# Tortoise_Matrix_Board_schematic.net
KiCad netlist of a schematic drawn in EasyEDA
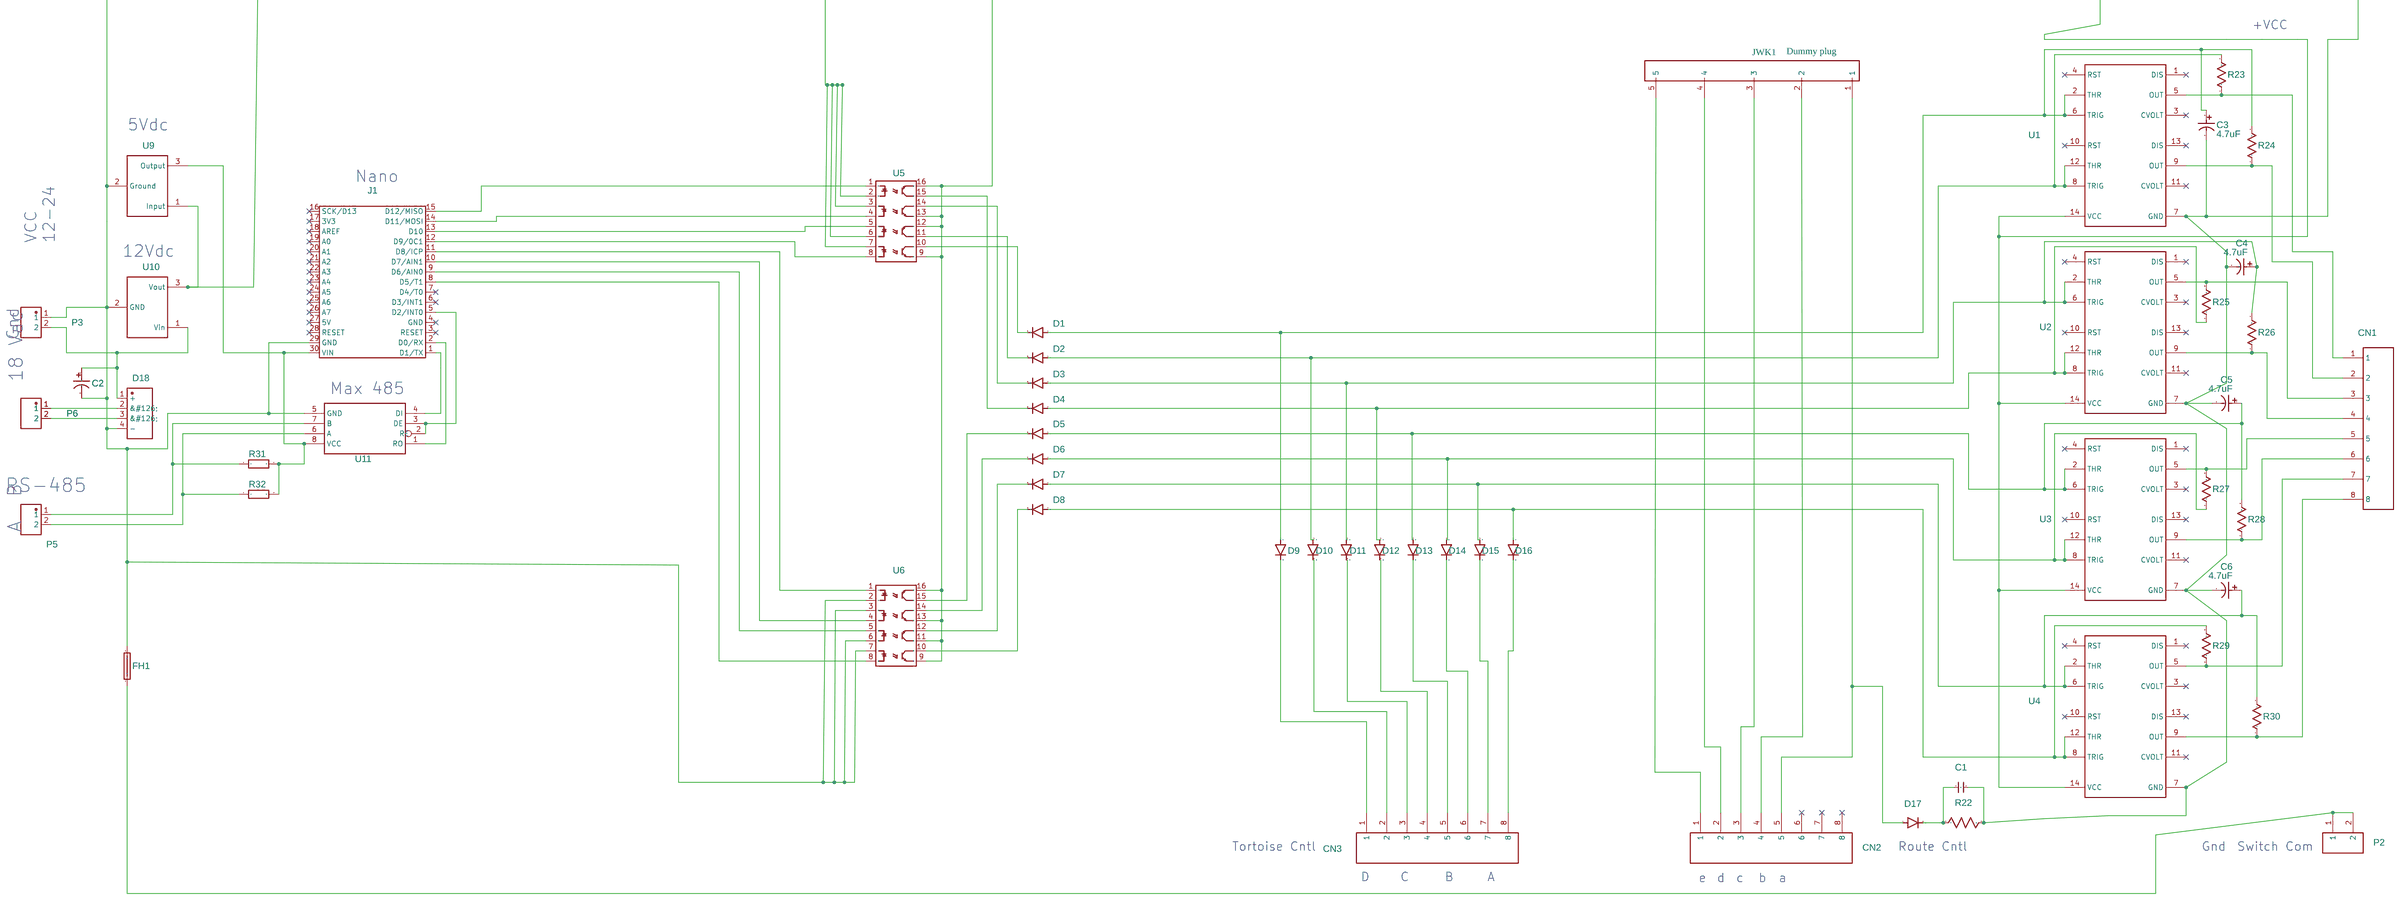
[diagram p0: schematic sheet]

(export (version "E")
  (design (tool "Eeschema 10.0.6"))
  (components
    (comp (ref "C1")
      (value "100pF")
      (fields
        (field (name "BOM_Manufacturer Part") "101K/1KV Capacitor")
        (field (name "BOM_Supplier Part") "C3715")
      )
      (libsource (lib "") (part "Capacitor"))
    )
    (comp (ref "C2")
      (value "470uF")
      (fields
        (field (name "BOM_Manufacturer Part") "470uF 100V 16*25")
        (field (name "BOM_Supplier Part") "C72551")
      )
      (libsource (lib "") (part "470uF 100V 16*25"))
    )
    (comp (ref "C3")
      (value "4.7uF")
      (fields
        (field (name "BOM_Manufacturer Part") "4.7uF 50V 4*7")
        (field (name "BOM_Supplier Part") "C43841")
      )
      (libsource (lib "") (part "4.7uF 50V 4*7_1"))
    )
    (comp (ref "C4")
      (value "4.7uF")
      (fields
        (field (name "BOM_Manufacturer Part") "4.7uF 50V 4*7")
        (field (name "BOM_Supplier Part") "C43841")
      )
      (libsource (lib "") (part "4.7uF 50V 4*7"))
    )
    (comp (ref "C5")
      (value "4.7uF")
      (fields
        (field (name "BOM_Manufacturer Part") "4.7uF 50V 4*7")
        (field (name "BOM_Supplier Part") "C43841")
      )
      (libsource (lib "") (part "4.7uF 50V 4*7"))
    )
    (comp (ref "C6")
      (value "4.7uF")
      (fields
        (field (name "BOM_Manufacturer Part") "4.7uF 50V 4*7")
        (field (name "BOM_Supplier Part") "C43841")
      )
      (libsource (lib "") (part "4.7uF 50V 4*7"))
    )
    (comp (ref "CN1")
      (value "WJ25C-B-7.62-8P-13-00A")
      (fields (field (name "BOM_Supplier Part") "C49492"))
      (libsource (lib "") (part "Unknown_1845_850"))
    )
    (comp (ref "CN2")
      (value "WJ25C-B-7.62-8P-13-00A")
      (fields (field (name "BOM_Supplier Part") "C49492"))
      (libsource (lib "") (part "Unknown_1260_1250"))
    )
    (comp (ref "CN3")
      (value "WJ25C-B-7.62-8P-13-00A")
      (fields (field (name "BOM_Supplier Part") "C49492"))
      (libsource (lib "") (part "Unknown_930_1250"))
    )
    (comp (ref "D1")
      (value "DIODE")
      (fields (field (name "BOM_Manufacturer Part") "?"))
      (libsource (lib "") (part "Unknown_535_755"))
    )
    (comp (ref "D2")
      (value "DIODE")
      (fields (field (name "BOM_Manufacturer Part") "?"))
      (libsource (lib "") (part "Unknown_535_780"))
    )
    (comp (ref "D3")
      (value "DIODE")
      (fields (field (name "BOM_Manufacturer Part") "?"))
      (libsource (lib "") (part "Unknown_535_805"))
    )
    (comp (ref "D4")
      (value "DIODE")
      (fields (field (name "BOM_Manufacturer Part") "?"))
      (libsource (lib "") (part "Unknown_535_830"))
    )
    (comp (ref "D5")
      (value "DIODE")
      (fields (field (name "BOM_Manufacturer Part") "?"))
      (libsource (lib "") (part "Unknown_535_855"))
    )
    (comp (ref "D6")
      (value "DIODE")
      (fields (field (name "BOM_Manufacturer Part") "?"))
      (libsource (lib "") (part "Unknown_535_880"))
    )
    (comp (ref "D7")
      (value "DIODE")
      (fields (field (name "BOM_Manufacturer Part") "?"))
      (libsource (lib "") (part "Unknown_535_905"))
    )
    (comp (ref "D8")
      (value "DIODE")
      (fields (field (name "BOM_Manufacturer Part") "?"))
      (libsource (lib "") (part "Unknown_535_930"))
    )
    (comp (ref "D9")
      (value "DIODE")
      (fields (field (name "BOM_Manufacturer Part") "?"))
      (libsource (lib "") (part "Unknown_775_970"))
    )
    (comp (ref "D10")
      (value "DIODE")
      (fields (field (name "BOM_Manufacturer Part") "?"))
      (libsource (lib "") (part "Unknown_808_970"))
    )
    (comp (ref "D11")
      (value "DIODE")
      (fields (field (name "BOM_Manufacturer Part") "?"))
      (libsource (lib "") (part "Unknown_841_970"))
    )
    (comp (ref "D12")
      (value "DIODE")
      (fields (field (name "BOM_Manufacturer Part") "?"))
      (libsource (lib "") (part "Unknown_874_970"))
    )
    (comp (ref "D13")
      (value "DIODE")
      (fields (field (name "BOM_Manufacturer Part") "?"))
      (libsource (lib "") (part "Unknown_906_970"))
    )
    (comp (ref "D14")
      (value "DIODE")
      (fields (field (name "BOM_Manufacturer Part") "?"))
      (libsource (lib "") (part "Unknown_939_970"))
    )
    (comp (ref "D15")
      (value "DIODE")
      (fields (field (name "BOM_Manufacturer Part") "?"))
      (libsource (lib "") (part "Unknown_972_970"))
    )
    (comp (ref "D16")
      (value "DIODE")
      (fields (field (name "BOM_Manufacturer Part") "?"))
      (libsource (lib "") (part "Unknown_1005_970"))
    )
    (comp (ref "D17")
      (value "DIODE")
      (fields (field (name "BOM_Manufacturer Part") "?"))
      (libsource (lib "") (part "Unknown_1400_1240"))
    )
    (comp (ref "D18")
      (value "D50SB100")
      (fields (field (name "BOM_Supplier Part") "C411148"))
      (libsource (lib "") (part "Unknown_-360_835"))
    )
    (comp (ref "FH1")
      (value "64600001003")
      (fields (field (name "BOM_Supplier Part") "C206887"))
      (libsource (lib "") (part "Unknown_-365_1085"))
    )
    (comp (ref "J1") (value "Arduino_Nano_Header") (libsource (lib "") (part "Unknown_-125_705")))
    (comp (ref "JWK1") (value "Dummy plug") (libsource (lib "") (part "Unknown_1240_504")))
    (comp (ref "P2")
      (value "WJ762-7.62-2P-13-00A")
      (fields (field (name "BOM_Supplier Part") "C72333"))
      (libsource (lib "") (part "Unknown_1825_1250"))
    )
    (comp (ref "P3")
      (value "WJ25C-B-2P")
      (fields (field (name "BOM_Supplier Part") "C8422"))
      (libsource (lib "") (part "Unknown_-460_745"))
    )
    (comp (ref "P5")
      (value "WJ25C-B-2P")
      (fields (field (name "BOM_Supplier Part") "C8422"))
      (libsource (lib "") (part "Unknown_-460_940"))
    )
    (comp (ref "P6")
      (value "WJ25C-B-2P")
      (fields (field (name "BOM_Supplier Part") "C8422"))
      (libsource (lib "") (part "Unknown_-460_835"))
    )
    (comp (ref "R22")
      (value "1k")
      (fields (field (name "BOM_Manufacturer Part") "?"))
      (libsource (lib "") (part "Res_AXIAL-0.3(1/8W)_US"))
    )
    (comp (ref "R23")
      (value "10k")
      (fields
        (field (name "BOM_Manufacturer Part") "RESISTOR_ALONG")
        (field (name "BOM_Supplier Part") "9339116")
      )
      (libsource (lib "") (part "Unknown_1705_500"))
    )
    (comp (ref "R24")
      (value "10k")
      (fields
        (field (name "BOM_Manufacturer Part") "RESISTOR_ALONG")
        (field (name "BOM_Supplier Part") "9339116")
      )
      (libsource (lib "") (part "Unknown_1735_570"))
    )
    (comp (ref "R25")
      (value "10k")
      (fields
        (field (name "BOM_Manufacturer Part") "RESISTOR_ALONG")
        (field (name "BOM_Supplier Part") "9339116")
      )
      (libsource (lib "") (part "Unknown_1690_725"))
    )
    (comp (ref "R26")
      (value "10k")
      (fields
        (field (name "BOM_Manufacturer Part") "RESISTOR_ALONG")
        (field (name "BOM_Supplier Part") "9339116")
      )
      (libsource (lib "") (part "Unknown_1735_755"))
    )
    (comp (ref "R27")
      (value "10k")
      (fields
        (field (name "BOM_Manufacturer Part") "RESISTOR_ALONG")
        (field (name "BOM_Supplier Part") "9339116")
      )
      (libsource (lib "") (part "Unknown_1690_910"))
    )
    (comp (ref "R28")
      (value "10k")
      (fields
        (field (name "BOM_Manufacturer Part") "RESISTOR_ALONG")
        (field (name "BOM_Supplier Part") "9339116")
      )
      (libsource (lib "") (part "Unknown_1725_940"))
    )
    (comp (ref "R29")
      (value "10k")
      (fields
        (field (name "BOM_Manufacturer Part") "RESISTOR_ALONG")
        (field (name "BOM_Supplier Part") "9339116")
      )
      (libsource (lib "") (part "Unknown_1690_1065"))
    )
    (comp (ref "R30")
      (value "10k")
      (fields
        (field (name "BOM_Manufacturer Part") "RESISTOR_ALONG")
        (field (name "BOM_Supplier Part") "9339116")
      )
      (libsource (lib "") (part "Unknown_1740_1135"))
    )
    (comp (ref "R31")
      (value "10K")
      (fields
        (field (name "BOM_Manufacturer Part") "CFR0W4J0103A50")
        (field (name "BOM_Supplier Part") "C61299")
      )
      (libsource (lib "") (part "CFR0W4J0103A50"))
    )
    (comp (ref "R32")
      (value "10K")
      (fields
        (field (name "BOM_Manufacturer Part") "CFR0W4J0103A50")
        (field (name "BOM_Supplier Part") "C61299")
      )
      (libsource (lib "") (part "CFR0W4J0103A50"))
    )
    (comp (ref "U1")
      (value "LM556CN")
      (fields (field (name "BOM_Manufacturer Part") "?"))
      (libsource (lib "") (part "Unknown_1610_570"))
    )
    (comp (ref "U2")
      (value "LM556CN")
      (fields (field (name "BOM_Manufacturer Part") "?"))
      (libsource (lib "") (part "Unknown_1610_755"))
    )
    (comp (ref "U3")
      (value "LM556CN")
      (fields (field (name "BOM_Manufacturer Part") "?"))
      (libsource (lib "") (part "Unknown_1610_940"))
    )
    (comp (ref "U4")
      (value "LM556CN")
      (fields (field (name "BOM_Manufacturer Part") "?"))
      (libsource (lib "") (part "Unknown_1610_1135"))
    )
    (comp (ref "U5")
      (value "Optocoupler_ILQ74 QUAD")
      (fields (field (name "BOM_Manufacturer Part") "?"))
      (libsource (lib "") (part "Unknown_395_645"))
    )
    (comp (ref "U6")
      (value "Optocoupler_ILQ74 QUAD")
      (fields (field (name "BOM_Manufacturer Part") "?"))
      (libsource (lib "") (part "Unknown_395_1045"))
    )
    (comp (ref "U9")
      (value "MC7805BTG")
      (fields (field (name "BOM_Supplier Part") "C45385"))
      (libsource (lib "") (part "Unknown_-345_610"))
    )
    (comp (ref "U10")
      (value "CJ7812")
      (fields (field (name "BOM_Supplier Part") "C77894"))
      (libsource (lib "") (part "Unknown_-345_730"))
    )
    (comp (ref "U11") (value "MAX485DIL") (libsource (lib "") (part "Unknown_-130_850")))
  )
  (nets
    (net (code "1") (name "Net-(C1-Pad1)") (class "Default")
      (node (ref "C1") (pin "1") (pinfunction "1_1") (pintype "unspecified"))
      (node (ref "D17") (pin "C") (pinfunction "C_C") (pintype "unspecified"))
      (node (ref "R22") (pin "1") (pinfunction "1_1") (pintype "unspecified"))
    )
    (net (code "2") (name "Net-(C3-Pad1)") (class "Default")
      (node (ref "C3") (pin "1") (pinfunction "1_1") (pintype "input"))
      (node (ref "D1") (pin "A") (pinfunction "A_A") (pintype "unspecified"))
      (node (ref "D9") (pin "A") (pinfunction "A_A") (pintype "unspecified"))
      (node (ref "R24") (pin "2") (pinfunction "2_2") (pintype "unspecified"))
      (node (ref "U1") (pin "2") (pinfunction "THR_2") (pintype "unspecified"))
      (node (ref "U1") (pin "6") (pinfunction "TRIG_6") (pintype "unspecified"))
    )
    (net (code "3") (name "Net-(C4-Pad1)") (class "Default")
      (node (ref "C4") (pin "1") (pinfunction "1_1") (pintype "input"))
      (node (ref "D11") (pin "A") (pinfunction "A_A") (pintype "unspecified"))
      (node (ref "D3") (pin "A") (pinfunction "A_A") (pintype "unspecified"))
      (node (ref "R26") (pin "2") (pinfunction "2_2") (pintype "unspecified"))
      (node (ref "U2") (pin "2") (pinfunction "THR_2") (pintype "unspecified"))
      (node (ref "U2") (pin "6") (pinfunction "TRIG_6") (pintype "unspecified"))
    )
    (net (code "4") (name "Net-(C5-Pad1)") (class "Default")
      (node (ref "C5") (pin "1") (pinfunction "1_1") (pintype "input"))
      (node (ref "D13") (pin "A") (pinfunction "A_A") (pintype "unspecified"))
      (node (ref "D5") (pin "A") (pinfunction "A_A") (pintype "unspecified"))
      (node (ref "R28") (pin "2") (pinfunction "2_2") (pintype "unspecified"))
      (node (ref "U3") (pin "2") (pinfunction "THR_2") (pintype "unspecified"))
      (node (ref "U3") (pin "6") (pinfunction "TRIG_6") (pintype "unspecified"))
    )
    (net (code "5") (name "Net-(C6-Pad1)") (class "Default")
      (node (ref "C6") (pin "1") (pinfunction "1_1") (pintype "input"))
      (node (ref "D15") (pin "A") (pinfunction "A_A") (pintype "unspecified"))
      (node (ref "D7") (pin "A") (pinfunction "A_A") (pintype "unspecified"))
      (node (ref "R30") (pin "2") (pinfunction "2_2") (pintype "unspecified"))
      (node (ref "U4") (pin "2") (pinfunction "THR_2") (pintype "unspecified"))
      (node (ref "U4") (pin "6") (pinfunction "TRIG_6") (pintype "unspecified"))
    )
    (net (code "6") (name "Net-(CN1-Pad1)") (class "Default")
      (node (ref "CN1") (pin "1") (pinfunction "1_1") (pintype "input"))
      (node (ref "R23") (pin "1") (pinfunction "1_1") (pintype "unspecified"))
      (node (ref "U1") (pin "5") (pinfunction "OUT_5") (pintype "output"))
    )
    (net (code "7") (name "Net-(CN1-Pad2)") (class "Default")
      (node (ref "CN1") (pin "2") (pinfunction "2_2") (pintype "input"))
      (node (ref "R24") (pin "1") (pinfunction "1_1") (pintype "unspecified"))
      (node (ref "U1") (pin "9") (pinfunction "OUT_9") (pintype "output"))
    )
    (net (code "8") (name "Net-(CN1-Pad3)") (class "Default")
      (node (ref "CN1") (pin "3") (pinfunction "3_3") (pintype "input"))
      (node (ref "R25") (pin "2") (pinfunction "2_2") (pintype "unspecified"))
      (node (ref "U2") (pin "5") (pinfunction "OUT_5") (pintype "output"))
    )
    (net (code "9") (name "Net-(CN1-Pad4)") (class "Default")
      (node (ref "CN1") (pin "4") (pinfunction "4_4") (pintype "input"))
      (node (ref "R26") (pin "1") (pinfunction "1_1") (pintype "unspecified"))
      (node (ref "U2") (pin "9") (pinfunction "OUT_9") (pintype "output"))
    )
    (net (code "10") (name "Net-(CN1-Pad5)") (class "Default")
      (node (ref "CN1") (pin "5") (pinfunction "5_5") (pintype "input"))
      (node (ref "R27") (pin "2") (pinfunction "2_2") (pintype "unspecified"))
      (node (ref "U3") (pin "5") (pinfunction "OUT_5") (pintype "output"))
    )
    (net (code "11") (name "Net-(CN1-Pad6)") (class "Default")
      (node (ref "CN1") (pin "6") (pinfunction "6_6") (pintype "input"))
      (node (ref "R28") (pin "1") (pinfunction "1_1") (pintype "unspecified"))
      (node (ref "U3") (pin "9") (pinfunction "OUT_9") (pintype "output"))
    )
    (net (code "12") (name "Net-(CN1-Pad7)") (class "Default")
      (node (ref "CN1") (pin "7") (pinfunction "7_7") (pintype "input"))
      (node (ref "R29") (pin "1") (pinfunction "1_1") (pintype "unspecified"))
      (node (ref "U4") (pin "5") (pinfunction "OUT_5") (pintype "output"))
    )
    (net (code "13") (name "Net-(CN1-Pad8)") (class "Default")
      (node (ref "CN1") (pin "8") (pinfunction "8_8") (pintype "input"))
      (node (ref "R30") (pin "1") (pinfunction "1_1") (pintype "unspecified"))
      (node (ref "U4") (pin "9") (pinfunction "OUT_9") (pintype "output"))
    )
    (net (code "14") (name "Net-(CN2-Pad1)") (class "Default")
      (node (ref "CN2") (pin "1") (pinfunction "1_1") (pintype "input"))
      (node (ref "JWK1") (pin "5") (pinfunction "5_5") (pintype "unspecified"))
    )
    (net (code "15") (name "Net-(CN2-Pad2)") (class "Default")
      (node (ref "CN2") (pin "2") (pinfunction "2_2") (pintype "input"))
      (node (ref "JWK1") (pin "4") (pinfunction "4_4") (pintype "unspecified"))
    )
    (net (code "16") (name "Net-(CN2-Pad3)") (class "Default")
      (node (ref "CN2") (pin "3") (pinfunction "3_3") (pintype "input"))
      (node (ref "JWK1") (pin "3") (pinfunction "3_3") (pintype "unspecified"))
    )
    (net (code "17") (name "Net-(CN2-Pad4)") (class "Default")
      (node (ref "CN2") (pin "4") (pinfunction "4_4") (pintype "input"))
      (node (ref "JWK1") (pin "2") (pinfunction "2_2") (pintype "unspecified"))
    )
    (net (code "18") (name "Net-(CN2-Pad5)") (class "Default")
      (node (ref "CN2") (pin "5") (pinfunction "5_5") (pintype "input"))
      (node (ref "D17") (pin "A") (pinfunction "A_A") (pintype "unspecified"))
      (node (ref "JWK1") (pin "1") (pinfunction "1_1") (pintype "unspecified"))
    )
    (net (code "19") (name "Net-(CN3-Pad1)") (class "Default")
      (node (ref "CN3") (pin "1") (pinfunction "1_1") (pintype "input"))
      (node (ref "D9") (pin "C") (pinfunction "C_C") (pintype "unspecified"))
    )
    (net (code "20") (name "Net-(CN3-Pad2)") (class "Default")
      (node (ref "CN3") (pin "2") (pinfunction "2_2") (pintype "input"))
      (node (ref "D10") (pin "C") (pinfunction "C_C") (pintype "unspecified"))
    )
    (net (code "21") (name "Net-(CN3-Pad3)") (class "Default")
      (node (ref "CN3") (pin "3") (pinfunction "3_3") (pintype "input"))
      (node (ref "D11") (pin "C") (pinfunction "C_C") (pintype "unspecified"))
    )
    (net (code "22") (name "Net-(CN3-Pad4)") (class "Default")
      (node (ref "CN3") (pin "4") (pinfunction "4_4") (pintype "input"))
      (node (ref "D12") (pin "C") (pinfunction "C_C") (pintype "unspecified"))
    )
    (net (code "23") (name "Net-(CN3-Pad5)") (class "Default")
      (node (ref "CN3") (pin "5") (pinfunction "5_5") (pintype "input"))
      (node (ref "D13") (pin "C") (pinfunction "C_C") (pintype "unspecified"))
    )
    (net (code "24") (name "Net-(CN3-Pad6)") (class "Default")
      (node (ref "CN3") (pin "6") (pinfunction "6_6") (pintype "input"))
      (node (ref "D14") (pin "C") (pinfunction "C_C") (pintype "unspecified"))
    )
    (net (code "25") (name "Net-(CN3-Pad7)") (class "Default")
      (node (ref "CN3") (pin "7") (pinfunction "7_7") (pintype "input"))
      (node (ref "D15") (pin "C") (pinfunction "C_C") (pintype "unspecified"))
    )
    (net (code "26") (name "Net-(CN3-Pad8)") (class "Default")
      (node (ref "CN3") (pin "8") (pinfunction "8_8") (pintype "input"))
      (node (ref "D16") (pin "C") (pinfunction "C_C") (pintype "unspecified"))
    )
    (net (code "27") (name "Net-(D1-PadC)") (class "Default")
      (node (ref "D1") (pin "C") (pinfunction "C_C") (pintype "unspecified"))
      (node (ref "U5") (pin "10") (pinfunction "10_10") (pintype "unspecified"))
    )
    (net (code "28") (name "Net-(D2-PadC)") (class "Default")
      (node (ref "D2") (pin "C") (pinfunction "C_C") (pintype "unspecified"))
      (node (ref "U5") (pin "11") (pinfunction "11_11") (pintype "unspecified"))
    )
    (net (code "29") (name "Net-(D3-PadC)") (class "Default")
      (node (ref "D3") (pin "C") (pinfunction "C_C") (pintype "unspecified"))
      (node (ref "U5") (pin "14") (pinfunction "14_14") (pintype "unspecified"))
    )
    (net (code "30") (name "Net-(D4-PadC)") (class "Default")
      (node (ref "D4") (pin "C") (pinfunction "C_C") (pintype "unspecified"))
      (node (ref "U5") (pin "15") (pinfunction "15_15") (pintype "unspecified"))
    )
    (net (code "31") (name "Net-(D5-PadC)") (class "Default")
      (node (ref "D5") (pin "C") (pinfunction "C_C") (pintype "unspecified"))
      (node (ref "U6") (pin "15") (pinfunction "15_15") (pintype "unspecified"))
    )
    (net (code "32") (name "Net-(D6-PadC)") (class "Default")
      (node (ref "D6") (pin "C") (pinfunction "C_C") (pintype "unspecified"))
      (node (ref "U6") (pin "14") (pinfunction "14_14") (pintype "unspecified"))
    )
    (net (code "33") (name "Net-(D7-PadC)") (class "Default")
      (node (ref "D7") (pin "C") (pinfunction "C_C") (pintype "unspecified"))
      (node (ref "U6") (pin "12") (pinfunction "12_12") (pintype "unspecified"))
    )
    (net (code "34") (name "Net-(D8-PadC)") (class "Default")
      (node (ref "D8") (pin "C") (pinfunction "C_C") (pintype "unspecified"))
      (node (ref "U6") (pin "10") (pinfunction "10_10") (pintype "unspecified"))
    )
    (net (code "35") (name "Net-(D10-PadA)") (class "Default")
      (node (ref "D10") (pin "A") (pinfunction "A_A") (pintype "unspecified"))
      (node (ref "D2") (pin "A") (pinfunction "A_A") (pintype "unspecified"))
      (node (ref "R23") (pin "2") (pinfunction "2_2") (pintype "unspecified"))
      (node (ref "U1") (pin "12") (pinfunction "THR_12") (pintype "unspecified"))
      (node (ref "U1") (pin "8") (pinfunction "TRIG_8") (pintype "unspecified"))
    )
    (net (code "36") (name "Net-(D12-PadA)") (class "Default")
      (node (ref "D12") (pin "A") (pinfunction "A_A") (pintype "unspecified"))
      (node (ref "D4") (pin "A") (pinfunction "A_A") (pintype "unspecified"))
      (node (ref "R25") (pin "1") (pinfunction "1_1") (pintype "unspecified"))
      (node (ref "U2") (pin "12") (pinfunction "THR_12") (pintype "unspecified"))
      (node (ref "U2") (pin "8") (pinfunction "TRIG_8") (pintype "unspecified"))
    )
    (net (code "37") (name "Net-(D14-PadA)") (class "Default")
      (node (ref "D14") (pin "A") (pinfunction "A_A") (pintype "unspecified"))
      (node (ref "D6") (pin "A") (pinfunction "A_A") (pintype "unspecified"))
      (node (ref "R27") (pin "1") (pinfunction "1_1") (pintype "unspecified"))
      (node (ref "U3") (pin "12") (pinfunction "THR_12") (pintype "unspecified"))
      (node (ref "U3") (pin "8") (pinfunction "TRIG_8") (pintype "unspecified"))
    )
    (net (code "38") (name "Net-(D16-PadA)") (class "Default")
      (node (ref "D16") (pin "A") (pinfunction "A_A") (pintype "unspecified"))
      (node (ref "D8") (pin "A") (pinfunction "A_A") (pintype "unspecified"))
      (node (ref "R29") (pin "2") (pinfunction "2_2") (pintype "unspecified"))
      (node (ref "U4") (pin "12") (pinfunction "THR_12") (pintype "unspecified"))
      (node (ref "U4") (pin "8") (pinfunction "TRIG_8") (pintype "unspecified"))
    )
    (net (code "39") (name "Net-(D18-&#126;-Pad2)") (class "Default")
      (node (ref "D18") (pin "2") (pinfunction "&#126;_2") (pintype "unspecified"))
      (node (ref "P6") (pin "1") (pinfunction "1_1") (pintype "unspecified"))
    )
    (net (code "40") (name "Net-(D18-&#126;-Pad3)") (class "Default")
      (node (ref "D18") (pin "3") (pinfunction "&#126;_3") (pintype "unspecified"))
      (node (ref "P6") (pin "2") (pinfunction "2_2") (pintype "unspecified"))
    )
    (net (code "41") (name "Net-(D18-+)") (class "Default")
      (node (ref "C2") (pin "1") (pinfunction "1_1") (pintype "input"))
      (node (ref "D18") (pin "1") (pinfunction "+_1") (pintype "unspecified"))
      (node (ref "P3") (pin "2") (pinfunction "2_2") (pintype "unspecified"))
      (node (ref "U10") (pin "1") (pinfunction "Vin_1") (pintype "unspecified"))
    )
    (net (code "42") (name "Net-(D18--)") (class "Default")
      (node (ref "C1") (pin "2") (pinfunction "2_2") (pintype "unspecified"))
      (node (ref "C2") (pin "2") (pinfunction "2_2") (pintype "input"))
      (node (ref "C3") (pin "2") (pinfunction "2_2") (pintype "input"))
      (node (ref "C4") (pin "2") (pinfunction "2_2") (pintype "input"))
      (node (ref "C5") (pin "2") (pinfunction "2_2") (pintype "input"))
      (node (ref "C6") (pin "2") (pinfunction "2_2") (pintype "input"))
      (node (ref "D18") (pin "4") (pinfunction "-_4") (pintype "unspecified"))
      (node (ref "FH1") (pin "2") (pinfunction "2_2") (pintype "unspecified"))
      (node (ref "J1") (pin "29") (pinfunction "GND_29") (pintype "unspecified"))
      (node (ref "P3") (pin "1") (pinfunction "1_1") (pintype "unspecified"))
      (node (ref "R22") (pin "2") (pinfunction "2_2") (pintype "unspecified"))
      (node (ref "U1") (pin "7") (pinfunction "GND_7") (pintype "passive"))
      (node (ref "U10") (pin "2") (pinfunction "GND_2") (pintype "unspecified"))
      (node (ref "U11") (pin "5") (pinfunction "GND_5") (pintype "unspecified"))
      (node (ref "U2") (pin "7") (pinfunction "GND_7") (pintype "passive"))
      (node (ref "U3") (pin "7") (pinfunction "GND_7") (pintype "passive"))
      (node (ref "U4") (pin "7") (pinfunction "GND_7") (pintype "passive"))
      (node (ref "U5") (pin "12") (pinfunction "12_12") (pintype "unspecified"))
      (node (ref "U5") (pin "13") (pinfunction "13_13") (pintype "unspecified"))
      (node (ref "U5") (pin "16") (pinfunction "16_16") (pintype "unspecified"))
      (node (ref "U5") (pin "2") (pinfunction "2_2") (pintype "unspecified"))
      (node (ref "U5") (pin "3") (pinfunction "3_3") (pintype "unspecified"))
      (node (ref "U5") (pin "6") (pinfunction "6_6") (pintype "unspecified"))
      (node (ref "U5") (pin "7") (pinfunction "7_7") (pintype "unspecified"))
      (node (ref "U5") (pin "9") (pinfunction "9_9") (pintype "unspecified"))
      (node (ref "U6") (pin "11") (pinfunction "11_11") (pintype "unspecified"))
      (node (ref "U6") (pin "13") (pinfunction "13_13") (pintype "unspecified"))
      (node (ref "U6") (pin "16") (pinfunction "16_16") (pintype "unspecified"))
      (node (ref "U6") (pin "2") (pinfunction "2_2") (pintype "unspecified"))
      (node (ref "U6") (pin "3") (pinfunction "3_3") (pintype "unspecified"))
      (node (ref "U6") (pin "6") (pinfunction "6_6") (pintype "unspecified"))
      (node (ref "U6") (pin "7") (pinfunction "7_7") (pintype "unspecified"))
      (node (ref "U6") (pin "9") (pinfunction "9_9") (pintype "unspecified"))
      (node (ref "U9") (pin "2") (pinfunction "Ground_2") (pintype "unspecified"))
    )
    (net (code "43") (name "Net-(FH1-Pad1)") (class "Default")
      (node (ref "FH1") (pin "1") (pinfunction "1_1") (pintype "unspecified"))
      (node (ref "P2") (pin "1") (pinfunction "1_1") (pintype "unspecified"))
      (node (ref "P2") (pin "2") (pinfunction "2_2") (pintype "unspecified"))
    )
    (net (code "44") (name "Net-(J1-D0{slash}RX)") (class "Default")
      (node (ref "J1") (pin "2") (pinfunction "D0/RX_2") (pintype "unspecified"))
      (node (ref "U11") (pin "1") (pinfunction "RO_1") (pintype "unspecified"))
    )
    (net (code "45") (name "Net-(J1-D1{slash}TX)") (class "Default")
      (node (ref "J1") (pin "1") (pinfunction "D1/TX_1") (pintype "unspecified"))
      (node (ref "U11") (pin "4") (pinfunction "DI_4") (pintype "unspecified"))
    )
    (net (code "46") (name "Net-(J1-D2{slash}INT0)") (class "Default")
      (node (ref "J1") (pin "5") (pinfunction "D2/INT0_5") (pintype "unspecified"))
      (node (ref "U11") (pin "2") (pinfunction "RE_2") (pintype "unspecified"))
      (node (ref "U11") (pin "3") (pinfunction "DE_3") (pintype "unspecified"))
    )
    (net (code "47") (name "Net-(J1-D5{slash}T1)") (class "Default")
      (node (ref "J1") (pin "8") (pinfunction "D5/T1_8") (pintype "unspecified"))
      (node (ref "U6") (pin "8") (pinfunction "8_8") (pintype "unspecified"))
    )
    (net (code "48") (name "Net-(J1-D6{slash}AIN0)") (class "Default")
      (node (ref "J1") (pin "9") (pinfunction "D6/AIN0_9") (pintype "unspecified"))
      (node (ref "U6") (pin "5") (pinfunction "5_5") (pintype "unspecified"))
    )
    (net (code "49") (name "Net-(J1-D7{slash}AIN1)") (class "Default")
      (node (ref "J1") (pin "10") (pinfunction "D7/AIN1_10") (pintype "unspecified"))
      (node (ref "U6") (pin "4") (pinfunction "4_4") (pintype "unspecified"))
    )
    (net (code "50") (name "Net-(J1-D8{slash}ICP)") (class "Default")
      (node (ref "J1") (pin "11") (pinfunction "D8/ICP_11") (pintype "unspecified"))
      (node (ref "U6") (pin "1") (pinfunction "1_1") (pintype "unspecified"))
    )
    (net (code "51") (name "Net-(J1-D9{slash}0C1)") (class "Default")
      (node (ref "J1") (pin "12") (pinfunction "D9/0C1_12") (pintype "unspecified"))
      (node (ref "U5") (pin "8") (pinfunction "8_8") (pintype "unspecified"))
    )
    (net (code "52") (name "Net-(J1-D10)") (class "Default")
      (node (ref "J1") (pin "13") (pinfunction "D10_13") (pintype "unspecified"))
      (node (ref "U5") (pin "5") (pinfunction "5_5") (pintype "unspecified"))
    )
    (net (code "53") (name "Net-(J1-D11{slash}MOSI)") (class "Default")
      (node (ref "J1") (pin "14") (pinfunction "D11/MOSI_14") (pintype "unspecified"))
      (node (ref "U5") (pin "4") (pinfunction "4_4") (pintype "unspecified"))
    )
    (net (code "54") (name "Net-(J1-D12{slash}MISO)") (class "Default")
      (node (ref "J1") (pin "15") (pinfunction "D12/MISO_15") (pintype "unspecified"))
      (node (ref "U5") (pin "1") (pinfunction "1_1") (pintype "unspecified"))
    )
    (net (code "55") (name "Net-(J1-VIN)") (class "Default")
      (node (ref "J1") (pin "30") (pinfunction "VIN_30") (pintype "unspecified"))
      (node (ref "R31") (pin "2") (pinfunction "2_2") (pintype "input"))
      (node (ref "R32") (pin "2") (pinfunction "2_2") (pintype "input"))
      (node (ref "U11") (pin "8") (pinfunction "VCC_8") (pintype "unspecified"))
      (node (ref "U9") (pin "3") (pinfunction "Output_3") (pintype "unspecified"))
    )
    (net (code "56") (name "Net-(U1-VCC)") (class "Default")
      (node (ref "U1") (pin "14") (pinfunction "VCC_14") (pintype "passive"))
      (node (ref "U10") (pin "3") (pinfunction "Vout_3") (pintype "unspecified"))
      (node (ref "U2") (pin "14") (pinfunction "VCC_14") (pintype "passive"))
      (node (ref "U3") (pin "14") (pinfunction "VCC_14") (pintype "passive"))
      (node (ref "U4") (pin "14") (pinfunction "VCC_14") (pintype "passive"))
      (node (ref "U9") (pin "1") (pinfunction "Input_1") (pintype "unspecified"))
    )
    (net (code "57") (name "Net-(U11-A)") (class "Default")
      (node (ref "P5") (pin "2") (pinfunction "2_2") (pintype "unspecified"))
      (node (ref "R32") (pin "1") (pinfunction "1_1") (pintype "input"))
      (node (ref "U11") (pin "6") (pinfunction "A_6") (pintype "unspecified"))
    )
    (net (code "58") (name "Net-(U11-B)") (class "Default")
      (node (ref "P5") (pin "1") (pinfunction "1_1") (pintype "unspecified"))
      (node (ref "R31") (pin "1") (pinfunction "1_1") (pintype "input"))
      (node (ref "U11") (pin "7") (pinfunction "B_7") (pintype "unspecified"))
    )
    (net (code "59") (name "unconnected-(CN2-Pad6)") (class "Default")
      (node (ref "CN2") (pin "6") (pinfunction "6_6") (pintype "input+no_connect"))
    )
    (net (code "60") (name "unconnected-(CN2-Pad7)") (class "Default")
      (node (ref "CN2") (pin "7") (pinfunction "7_7") (pintype "input+no_connect"))
    )
    (net (code "61") (name "unconnected-(CN2-Pad8)") (class "Default")
      (node (ref "CN2") (pin "8") (pinfunction "8_8") (pintype "input+no_connect"))
    )
    (net (code "62") (name "unconnected-(J1-3V3-Pad17)") (class "Default")
      (node (ref "J1") (pin "17") (pinfunction "3V3_17") (pintype "unspecified+no_connect"))
    )
    (net (code "63") (name "unconnected-(J1-5V-Pad27)") (class "Default")
      (node (ref "J1") (pin "27") (pinfunction "5V_27") (pintype "unspecified+no_connect"))
    )
    (net (code "64") (name "unconnected-(J1-A0-Pad19)") (class "Default")
      (node (ref "J1") (pin "19") (pinfunction "A0_19") (pintype "unspecified+no_connect"))
    )
    (net (code "65") (name "unconnected-(J1-A1-Pad20)") (class "Default")
      (node (ref "J1") (pin "20") (pinfunction "A1_20") (pintype "unspecified+no_connect"))
    )
    (net (code "66") (name "unconnected-(J1-A2-Pad21)") (class "Default")
      (node (ref "J1") (pin "21") (pinfunction "A2_21") (pintype "unspecified+no_connect"))
    )
    (net (code "67") (name "unconnected-(J1-A3-Pad22)") (class "Default")
      (node (ref "J1") (pin "22") (pinfunction "A3_22") (pintype "unspecified+no_connect"))
    )
    (net (code "68") (name "unconnected-(J1-A4-Pad23)") (class "Default")
      (node (ref "J1") (pin "23") (pinfunction "A4_23") (pintype "unspecified+no_connect"))
    )
    (net (code "69") (name "unconnected-(J1-A5-Pad24)") (class "Default")
      (node (ref "J1") (pin "24") (pinfunction "A5_24") (pintype "unspecified+no_connect"))
    )
    (net (code "70") (name "unconnected-(J1-A6-Pad25)") (class "Default")
      (node (ref "J1") (pin "25") (pinfunction "A6_25") (pintype "unspecified+no_connect"))
    )
    (net (code "71") (name "unconnected-(J1-A7-Pad26)") (class "Default")
      (node (ref "J1") (pin "26") (pinfunction "A7_26") (pintype "unspecified+no_connect"))
    )
    (net (code "72") (name "unconnected-(J1-AREF-Pad18)") (class "Default")
      (node (ref "J1") (pin "18") (pinfunction "AREF_18") (pintype "unspecified+no_connect"))
    )
    (net (code "73") (name "unconnected-(J1-D3{slash}INT1-Pad6)") (class "Default")
      (node (ref "J1") (pin "6") (pinfunction "D3/INT1_6") (pintype "unspecified+no_connect"))
    )
    (net (code "74") (name "unconnected-(J1-D4{slash}T0-Pad7)") (class "Default")
      (node (ref "J1") (pin "7") (pinfunction "D4/T0_7") (pintype "unspecified+no_connect"))
    )
    (net (code "75") (name "unconnected-(J1-GND-Pad4)") (class "Default")
      (node (ref "J1") (pin "4") (pinfunction "GND_4") (pintype "unspecified+no_connect"))
    )
    (net (code "76") (name "unconnected-(J1-RESET-Pad3)") (class "Default")
      (node (ref "J1") (pin "3") (pinfunction "RESET_3") (pintype "unspecified+no_connect"))
    )
    (net (code "77") (name "unconnected-(J1-RESET-Pad28)") (class "Default")
      (node (ref "J1") (pin "28") (pinfunction "RESET_28") (pintype "unspecified+no_connect"))
    )
    (net (code "78") (name "unconnected-(J1-SCK{slash}D13-Pad16)") (class "Default")
      (node (ref "J1") (pin "16") (pinfunction "SCK/D13_16") (pintype "unspecified+no_connect"))
    )
    (net (code "79") (name "unconnected-(U1-CVOLT-Pad3)") (class "Default")
      (node (ref "U1") (pin "3") (pinfunction "CVOLT_3") (pintype "unspecified+no_connect"))
    )
    (net (code "80") (name "unconnected-(U1-CVOLT-Pad11)") (class "Default")
      (node (ref "U1") (pin "11") (pinfunction "CVOLT_11") (pintype "unspecified+no_connect"))
    )
    (net (code "81") (name "unconnected-(U1-DIS-Pad1)") (class "Default")
      (node (ref "U1") (pin "1") (pinfunction "DIS_1") (pintype "unspecified+no_connect"))
    )
    (net (code "82") (name "unconnected-(U1-DIS-Pad13)") (class "Default")
      (node (ref "U1") (pin "13") (pinfunction "DIS_13") (pintype "unspecified+no_connect"))
    )
    (net (code "83") (name "unconnected-(U1-RST-Pad4)") (class "Default")
      (node (ref "U1") (pin "4") (pinfunction "RST_4") (pintype "unspecified+no_connect"))
    )
    (net (code "84") (name "unconnected-(U1-RST-Pad10)") (class "Default")
      (node (ref "U1") (pin "10") (pinfunction "RST_10") (pintype "unspecified+no_connect"))
    )
    (net (code "85") (name "unconnected-(U2-CVOLT-Pad3)") (class "Default")
      (node (ref "U2") (pin "3") (pinfunction "CVOLT_3") (pintype "unspecified+no_connect"))
    )
    (net (code "86") (name "unconnected-(U2-CVOLT-Pad11)") (class "Default")
      (node (ref "U2") (pin "11") (pinfunction "CVOLT_11") (pintype "unspecified+no_connect"))
    )
    (net (code "87") (name "unconnected-(U2-DIS-Pad1)") (class "Default")
      (node (ref "U2") (pin "1") (pinfunction "DIS_1") (pintype "unspecified+no_connect"))
    )
    (net (code "88") (name "unconnected-(U2-DIS-Pad13)") (class "Default")
      (node (ref "U2") (pin "13") (pinfunction "DIS_13") (pintype "unspecified+no_connect"))
    )
    (net (code "89") (name "unconnected-(U2-RST-Pad4)") (class "Default")
      (node (ref "U2") (pin "4") (pinfunction "RST_4") (pintype "unspecified+no_connect"))
    )
    (net (code "90") (name "unconnected-(U2-RST-Pad10)") (class "Default")
      (node (ref "U2") (pin "10") (pinfunction "RST_10") (pintype "unspecified+no_connect"))
    )
    (net (code "91") (name "unconnected-(U3-CVOLT-Pad3)") (class "Default")
      (node (ref "U3") (pin "3") (pinfunction "CVOLT_3") (pintype "unspecified+no_connect"))
    )
    (net (code "92") (name "unconnected-(U3-CVOLT-Pad11)") (class "Default")
      (node (ref "U3") (pin "11") (pinfunction "CVOLT_11") (pintype "unspecified+no_connect"))
    )
    (net (code "93") (name "unconnected-(U3-DIS-Pad1)") (class "Default")
      (node (ref "U3") (pin "1") (pinfunction "DIS_1") (pintype "unspecified+no_connect"))
    )
    (net (code "94") (name "unconnected-(U3-DIS-Pad13)") (class "Default")
      (node (ref "U3") (pin "13") (pinfunction "DIS_13") (pintype "unspecified+no_connect"))
    )
    (net (code "95") (name "unconnected-(U3-RST-Pad4)") (class "Default")
      (node (ref "U3") (pin "4") (pinfunction "RST_4") (pintype "unspecified+no_connect"))
    )
    (net (code "96") (name "unconnected-(U3-RST-Pad10)") (class "Default")
      (node (ref "U3") (pin "10") (pinfunction "RST_10") (pintype "unspecified+no_connect"))
    )
    (net (code "97") (name "unconnected-(U4-CVOLT-Pad3)") (class "Default")
      (node (ref "U4") (pin "3") (pinfunction "CVOLT_3") (pintype "unspecified+no_connect"))
    )
    (net (code "98") (name "unconnected-(U4-CVOLT-Pad11)") (class "Default")
      (node (ref "U4") (pin "11") (pinfunction "CVOLT_11") (pintype "unspecified+no_connect"))
    )
    (net (code "99") (name "unconnected-(U4-DIS-Pad1)") (class "Default")
      (node (ref "U4") (pin "1") (pinfunction "DIS_1") (pintype "unspecified+no_connect"))
    )
    (net (code "100") (name "unconnected-(U4-DIS-Pad13)") (class "Default")
      (node (ref "U4") (pin "13") (pinfunction "DIS_13") (pintype "unspecified+no_connect"))
    )
    (net (code "101") (name "unconnected-(U4-RST-Pad4)") (class "Default")
      (node (ref "U4") (pin "4") (pinfunction "RST_4") (pintype "unspecified+no_connect"))
    )
    (net (code "102") (name "unconnected-(U4-RST-Pad10)") (class "Default")
      (node (ref "U4") (pin "10") (pinfunction "RST_10") (pintype "unspecified+no_connect"))
    )
  )
)
